# ngh-power.net
KiCad netlist of a schematic drawn in Altium Designer
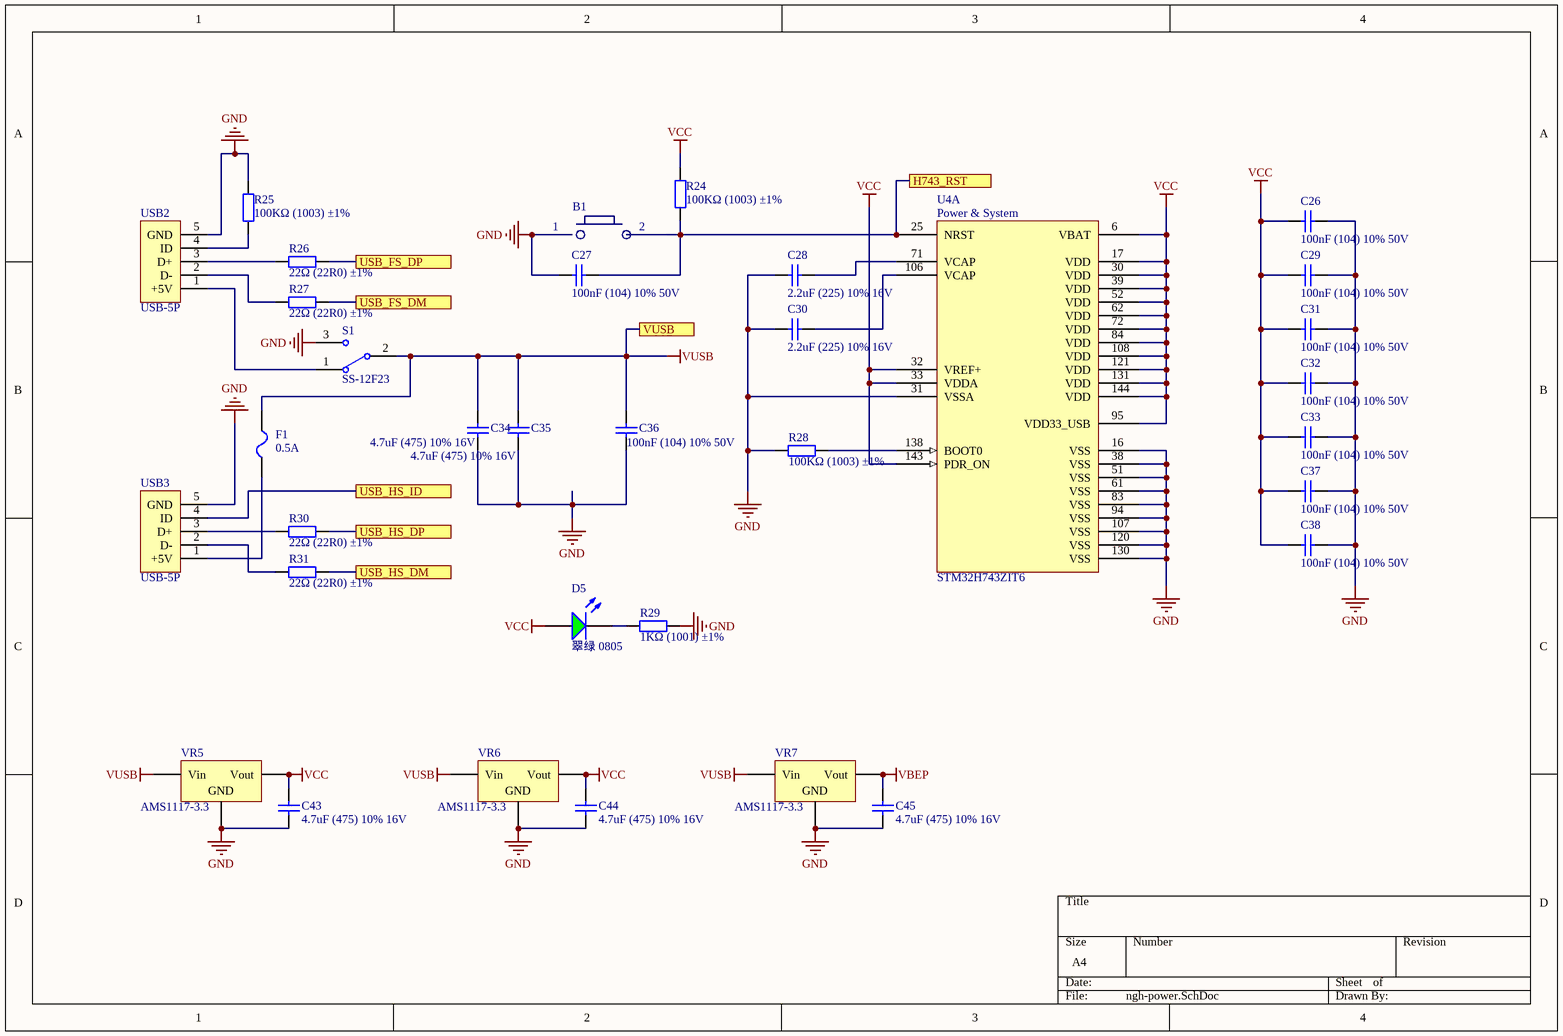
[diagram p0: ngh-power.SchDoc]

(export (version "E")
  (design (tool "Eeschema 10.0.6"))
  (components
    (comp (ref "B1")
      (value "B1")
      (footprint "MetalButton")
      (libsource (lib "MetalButton") (part "MetalButton"))
    )
    (comp (ref "C26")
      (value "100nF (104) 10% 50V")
      (footprint "0603_C")
      (description "贴片电容")
      (libsource (lib "Miscellaneous Devices LC") (part "0603 100nF (104) 10% 50V"))
    )
    (comp (ref "C27")
      (value "100nF (104) 10% 50V")
      (footprint "0603_C")
      (description "贴片电容")
      (libsource (lib "Miscellaneous Devices LC") (part "0603 100nF (104) 10% 50V"))
    )
    (comp (ref "C28")
      (value "2.2uF (225) 10% 16V")
      (footprint "0603_C")
      (description "贴片电容")
      (libsource (lib "Miscellaneous Devices LC") (part "0603 2.2uF (225) 10% 16V"))
    )
    (comp (ref "C29")
      (value "100nF (104) 10% 50V")
      (footprint "0603_C")
      (description "贴片电容")
      (libsource (lib "Miscellaneous Devices LC") (part "0603 100nF (104) 10% 50V"))
    )
    (comp (ref "C30")
      (value "2.2uF (225) 10% 16V")
      (footprint "0603_C")
      (description "贴片电容")
      (libsource (lib "Miscellaneous Devices LC") (part "0603 2.2uF (225) 10% 16V"))
    )
    (comp (ref "C31")
      (value "100nF (104) 10% 50V")
      (footprint "0603_C")
      (description "贴片电容")
      (libsource (lib "Miscellaneous Devices LC") (part "0603 100nF (104) 10% 50V"))
    )
    (comp (ref "C32")
      (value "100nF (104) 10% 50V")
      (footprint "0603_C")
      (description "贴片电容")
      (libsource (lib "Miscellaneous Devices LC") (part "0603 100nF (104) 10% 50V"))
    )
    (comp (ref "C33")
      (value "100nF (104) 10% 50V")
      (footprint "0603_C")
      (description "贴片电容")
      (libsource (lib "Miscellaneous Devices LC") (part "0603 100nF (104) 10% 50V"))
    )
    (comp (ref "C34")
      (value "4.7uF (475) 10% 16V")
      (footprint "0603_C")
      (description "贴片电容")
      (libsource (lib "Miscellaneous Devices LC") (part "0603 4.7uF (475) 10% 16V"))
    )
    (comp (ref "C35")
      (value "4.7uF (475) 10% 16V")
      (footprint "0603_C")
      (description "贴片电容")
      (libsource (lib "Miscellaneous Devices LC") (part "0603 4.7uF (475) 10% 16V"))
    )
    (comp (ref "C36")
      (value "100nF (104) 10% 50V")
      (footprint "0603_C")
      (description "贴片电容")
      (libsource (lib "Miscellaneous Devices LC") (part "0603 100nF (104) 10% 50V"))
    )
    (comp (ref "C37")
      (value "100nF (104) 10% 50V")
      (footprint "0603_C")
      (description "贴片电容")
      (libsource (lib "Miscellaneous Devices LC") (part "0603 100nF (104) 10% 50V"))
    )
    (comp (ref "C38")
      (value "100nF (104) 10% 50V")
      (footprint "0603_C")
      (description "贴片电容")
      (libsource (lib "Miscellaneous Devices LC") (part "0603 100nF (104) 10% 50V"))
    )
    (comp (ref "C43")
      (value "4.7uF (475) 10% 16V")
      (footprint "0603_C")
      (description "贴片电容")
      (libsource (lib "Miscellaneous Devices LC") (part "0603 4.7uF (475) 10% 16V"))
    )
    (comp (ref "C44")
      (value "4.7uF (475) 10% 16V")
      (footprint "0603_C")
      (description "贴片电容")
      (libsource (lib "Miscellaneous Devices LC") (part "0603 4.7uF (475) 10% 16V"))
    )
    (comp (ref "C45")
      (value "4.7uF (475) 10% 16V")
      (footprint "0603_C")
      (description "贴片电容")
      (libsource (lib "Miscellaneous Devices LC") (part "0603 4.7uF (475) 10% 16V"))
    )
    (comp (ref "D5")
      (value "翠绿 0805")
      (footprint "0805_LED_S1")
      (description "发光二极管")
      (libsource (lib "Miscellaneous Devices LC") (part "0805 翠绿"))
    )
    (comp (ref "F1")
      (value "0.5A")
      (footprint "FU 0603")
      (description "贴片保险丝")
      (fields (field (name "版权归属") "源创客"))
      (libsource (lib "10.1 - 保险丝-晶振") (part "FU"))
    )
    (comp (ref "R24")
      (value "100KΩ (1003) ±1%")
      (footprint "0603_R")
      (description "贴片电阻")
      (libsource (lib "Miscellaneous Devices LC") (part "0603 100KΩ (1003) 1%"))
    )
    (comp (ref "R25")
      (value "100KΩ (1003) ±1%")
      (footprint "0603_R")
      (description "贴片电阻")
      (libsource (lib "Miscellaneous Devices LC") (part "0603 100KΩ (1003) 1%"))
    )
    (comp (ref "R26")
      (value "22Ω (22R0) ±1%")
      (footprint "0603_R")
      (description "贴片电阻")
      (libsource (lib "Miscellaneous Devices LC") (part "0603 22Ω (22R0) 1%"))
    )
    (comp (ref "R27")
      (value "22Ω (22R0) ±1%")
      (footprint "0603_R")
      (description "贴片电阻")
      (libsource (lib "Miscellaneous Devices LC") (part "0603 22Ω (22R0) 1%"))
    )
    (comp (ref "R28")
      (value "100KΩ (1003) ±1%")
      (footprint "0603_R")
      (description "贴片电阻")
      (libsource (lib "") (part "0603 100KΩ (1003) 1%_1"))
    )
    (comp (ref "R29")
      (value "1KΩ (1001) ±1%")
      (footprint "0603_R")
      (description "贴片电阻")
      (libsource (lib "Miscellaneous Devices LC") (part "0603 1KΩ (1001) 1%"))
    )
    (comp (ref "R30")
      (value "22Ω (22R0) ±1%")
      (footprint "0603_R")
      (description "贴片电阻")
      (libsource (lib "Miscellaneous Devices LC") (part "0603 22Ω (22R0) 1%"))
    )
    (comp (ref "R31")
      (value "22Ω (22R0) ±1%")
      (footprint "0603_R")
      (description "贴片电阻")
      (libsource (lib "Miscellaneous Devices LC") (part "0603 22Ω (22R0) 1%"))
    )
    (comp (ref "S1")
      (value "SS-12F23")
      (footprint "SS-12F23")
      (description "1路波动开关")
      (fields (field (name "版权归属") "源创客"))
      (libsource (lib "5.1   - 按键-开关") (part "SSW-1P"))
    )
    (comp (ref "U4")
      (value "STM32H743ZIT6")
      (footprint "LQFP-144_20x20")
      (libsource (lib "STM32H743ZI") (part "STM32H743ZIT6"))
    )
    (comp (ref "USB2")
      (value "USB-5P")
      (footprint "USB-MICRO_D")
      (description "微型USB母座")
      (fields (field (name "版权归属") "源创客"))
      (libsource (lib "4.1   - 接口类") (part "USB-5P"))
    )
    (comp (ref "USB3")
      (value "USB-5P")
      (footprint "USB-MICRO_D")
      (description "微型USB母座")
      (fields (field (name "版权归属") "源创客"))
      (libsource (lib "4.1   - 接口类") (part "USB-5P"))
    )
    (comp (ref "VR5")
      (value "AMS1117-3.3")
      (footprint "SOT-223")
      (description "低压差线性稳压(LDO)")
      (libsource (lib "Miscellaneous Devices LC") (part "SOT-223 AMS1117-3.3"))
    )
    (comp (ref "VR6")
      (value "AMS1117-3.3")
      (footprint "SOT-223")
      (description "低压差线性稳压(LDO)")
      (libsource (lib "Miscellaneous Devices LC") (part "SOT-223 AMS1117-3.3"))
    )
    (comp (ref "VR7")
      (value "AMS1117-3.3")
      (footprint "SOT-223")
      (description "低压差线性稳压(LDO)")
      (libsource (lib "Miscellaneous Devices LC") (part "SOT-223 AMS1117-3.3"))
    )
  )
  (nets
    (net (code "1") (name "/H743_RST") (class "Default")
      (node (ref "B1") (pin "2") (pinfunction "2_2") (pintype "passive"))
      (node (ref "C27") (pin "2") (pinfunction "2_2") (pintype "passive"))
      (node (ref "R24") (pin "1") (pinfunction "1_1") (pintype "passive"))
      (node (ref "U4") (pin "25") (pinfunction "NRST_25") (pintype "power_in"))
    )
    (net (code "2") (name "/USB_FS_DM") (class "Default")
      (node (ref "R27") (pin "2") (pinfunction "2_2") (pintype "passive"))
    )
    (net (code "3") (name "/USB_FS_DP") (class "Default")
      (node (ref "R26") (pin "2") (pinfunction "2_2") (pintype "passive"))
    )
    (net (code "4") (name "/USB_HS_DM") (class "Default")
      (node (ref "R31") (pin "2") (pinfunction "2_2") (pintype "passive"))
    )
    (net (code "5") (name "/USB_HS_DP") (class "Default")
      (node (ref "R30") (pin "2") (pinfunction "2_2") (pintype "passive"))
    )
    (net (code "6") (name "/USB_HS_ID") (class "Default")
      (node (ref "USB3") (pin "4") (pinfunction "ID_4") (pintype "passive"))
    )
    (net (code "7") (name "GND") (class "Default")
      (node (ref "B1") (pin "1") (pinfunction "1_1") (pintype "passive"))
      (node (ref "C26") (pin "1") (pinfunction "1_1") (pintype "passive"))
      (node (ref "C27") (pin "1") (pinfunction "1_1") (pintype "passive"))
      (node (ref "C28") (pin "1") (pinfunction "1_1") (pintype "passive"))
      (node (ref "C29") (pin "1") (pinfunction "1_1") (pintype "passive"))
      (node (ref "C30") (pin "1") (pinfunction "1_1") (pintype "passive"))
      (node (ref "C31") (pin "1") (pinfunction "1_1") (pintype "passive"))
      (node (ref "C32") (pin "1") (pinfunction "1_1") (pintype "passive"))
      (node (ref "C33") (pin "1") (pinfunction "1_1") (pintype "passive"))
      (node (ref "C34") (pin "1") (pinfunction "1_1") (pintype "passive"))
      (node (ref "C35") (pin "1") (pinfunction "1_1") (pintype "passive"))
      (node (ref "C36") (pin "1") (pinfunction "1_1") (pintype "passive"))
      (node (ref "C37") (pin "1") (pinfunction "1_1") (pintype "passive"))
      (node (ref "C38") (pin "1") (pinfunction "1_1") (pintype "passive"))
      (node (ref "C43") (pin "1") (pinfunction "1_1") (pintype "passive"))
      (node (ref "C44") (pin "1") (pinfunction "1_1") (pintype "passive"))
      (node (ref "C45") (pin "1") (pinfunction "1_1") (pintype "passive"))
      (node (ref "R25") (pin "2") (pinfunction "2_2") (pintype "passive"))
      (node (ref "R28") (pin "2") (pinfunction "2_2") (pintype "passive"))
      (node (ref "R29") (pin "1") (pinfunction "1_1") (pintype "passive"))
      (node (ref "S1") (pin "3") (pinfunction "3_3") (pintype "passive"))
      (node (ref "U4") (pin "107") (pinfunction "VSS_107") (pintype "power_in"))
      (node (ref "U4") (pin "120") (pinfunction "VSS_120") (pintype "power_in"))
      (node (ref "U4") (pin "130") (pinfunction "VSS_130") (pintype "power_in"))
      (node (ref "U4") (pin "16") (pinfunction "VSS_16") (pintype "power_in"))
      (node (ref "U4") (pin "31") (pinfunction "VSSA_31") (pintype "power_in"))
      (node (ref "U4") (pin "38") (pinfunction "VSS_38") (pintype "power_in"))
      (node (ref "U4") (pin "51") (pinfunction "VSS_51") (pintype "power_in"))
      (node (ref "U4") (pin "61") (pinfunction "VSS_61") (pintype "power_in"))
      (node (ref "U4") (pin "83") (pinfunction "VSS_83") (pintype "power_in"))
      (node (ref "U4") (pin "94") (pinfunction "VSS_94") (pintype "power_in"))
      (node (ref "USB2") (pin "5") (pinfunction "GND_5") (pintype "passive"))
      (node (ref "USB3") (pin "5") (pinfunction "GND_5") (pintype "passive"))
      (node (ref "VR5") (pin "1") (pinfunction "GND_1") (pintype "passive"))
      (node (ref "VR6") (pin "1") (pinfunction "GND_1") (pintype "passive"))
      (node (ref "VR7") (pin "1") (pinfunction "GND_1") (pintype "passive"))
    )
    (net (code "8") (name "Net-(C28-Pad2)") (class "Default")
      (node (ref "C28") (pin "2") (pinfunction "2_2") (pintype "passive"))
      (node (ref "U4") (pin "71") (pinfunction "VCAP_71") (pintype "power_in"))
    )
    (net (code "9") (name "Net-(C30-Pad2)") (class "Default")
      (node (ref "C30") (pin "2") (pinfunction "2_2") (pintype "passive"))
      (node (ref "U4") (pin "106") (pinfunction "VCAP_106") (pintype "power_in"))
    )
    (net (code "10") (name "Net-(D5-PadK)") (class "Default")
      (node (ref "D5") (pin "K") (pinfunction "K_K") (pintype "passive"))
      (node (ref "R29") (pin "2") (pinfunction "2_2") (pintype "passive"))
    )
    (net (code "11") (name "Net-(U4A-BOOT0)") (class "Default")
      (node (ref "R28") (pin "1") (pinfunction "1_1") (pintype "passive"))
      (node (ref "U4") (pin "138") (pinfunction "BOOT0_138") (pintype "input"))
    )
    (net (code "12") (name "Net-(USB2-+5V)") (class "Default")
      (node (ref "S1") (pin "1") (pinfunction "1_1") (pintype "passive"))
      (node (ref "USB2") (pin "1") (pinfunction "+5V_1") (pintype "passive"))
    )
    (net (code "13") (name "Net-(USB2-D+)") (class "Default")
      (node (ref "R26") (pin "1") (pinfunction "1_1") (pintype "passive"))
      (node (ref "USB2") (pin "3") (pinfunction "D+_3") (pintype "passive"))
    )
    (net (code "14") (name "Net-(USB2-D-)") (class "Default")
      (node (ref "R27") (pin "1") (pinfunction "1_1") (pintype "passive"))
      (node (ref "USB2") (pin "2") (pinfunction "D-_2") (pintype "passive"))
    )
    (net (code "15") (name "Net-(USB2-ID)") (class "Default")
      (node (ref "R25") (pin "1") (pinfunction "1_1") (pintype "passive"))
      (node (ref "USB2") (pin "4") (pinfunction "ID_4") (pintype "passive"))
    )
    (net (code "16") (name "Net-(USB3-+5V)") (class "Default")
      (node (ref "F1") (pin "1") (pinfunction "1_1") (pintype "passive"))
      (node (ref "USB3") (pin "1") (pinfunction "+5V_1") (pintype "passive"))
    )
    (net (code "17") (name "Net-(USB3-D+)") (class "Default")
      (node (ref "R30") (pin "1") (pinfunction "1_1") (pintype "passive"))
      (node (ref "USB3") (pin "3") (pinfunction "D+_3") (pintype "passive"))
    )
    (net (code "18") (name "Net-(USB3-D-)") (class "Default")
      (node (ref "R31") (pin "1") (pinfunction "1_1") (pintype "passive"))
      (node (ref "USB3") (pin "2") (pinfunction "D-_2") (pintype "passive"))
    )
    (net (code "19") (name "VBEP") (class "Default")
      (node (ref "C45") (pin "2") (pinfunction "2_2") (pintype "passive"))
      (node (ref "VR7") (pin "2") (pinfunction "Vout_2") (pintype "passive"))
    )
    (net (code "20") (name "VCC") (class "Default")
      (node (ref "C26") (pin "2") (pinfunction "2_2") (pintype "passive"))
      (node (ref "C29") (pin "2") (pinfunction "2_2") (pintype "passive"))
      (node (ref "C31") (pin "2") (pinfunction "2_2") (pintype "passive"))
      (node (ref "C32") (pin "2") (pinfunction "2_2") (pintype "passive"))
      (node (ref "C33") (pin "2") (pinfunction "2_2") (pintype "passive"))
      (node (ref "C37") (pin "2") (pinfunction "2_2") (pintype "passive"))
      (node (ref "C38") (pin "2") (pinfunction "2_2") (pintype "passive"))
      (node (ref "C43") (pin "2") (pinfunction "2_2") (pintype "passive"))
      (node (ref "C44") (pin "2") (pinfunction "2_2") (pintype "passive"))
      (node (ref "D5") (pin "A") (pinfunction "A_A") (pintype "passive"))
      (node (ref "R24") (pin "2") (pinfunction "2_2") (pintype "passive"))
      (node (ref "U4") (pin "108") (pinfunction "VDD_108") (pintype "power_in"))
      (node (ref "U4") (pin "121") (pinfunction "VDD_121") (pintype "power_in"))
      (node (ref "U4") (pin "131") (pinfunction "VDD_131") (pintype "power_in"))
      (node (ref "U4") (pin "143") (pinfunction "PDR_ON_143") (pintype "input"))
      (node (ref "U4") (pin "144") (pinfunction "VDD_144") (pintype "power_in"))
      (node (ref "U4") (pin "17") (pinfunction "VDD_17") (pintype "power_in"))
      (node (ref "U4") (pin "30") (pinfunction "VDD_30") (pintype "power_in"))
      (node (ref "U4") (pin "32") (pinfunction "VREF+_32") (pintype "power_in"))
      (node (ref "U4") (pin "33") (pinfunction "VDDA_33") (pintype "power_in"))
      (node (ref "U4") (pin "39") (pinfunction "VDD_39") (pintype "power_in"))
      (node (ref "U4") (pin "52") (pinfunction "VDD_52") (pintype "power_in"))
      (node (ref "U4") (pin "6") (pinfunction "VBAT_6") (pintype "power_in"))
      (node (ref "U4") (pin "62") (pinfunction "VDD_62") (pintype "power_in"))
      (node (ref "U4") (pin "72") (pinfunction "VDD_72") (pintype "power_in"))
      (node (ref "U4") (pin "84") (pinfunction "VDD_84") (pintype "power_in"))
      (node (ref "U4") (pin "95") (pinfunction "VDD33_USB_95") (pintype "power_in"))
      (node (ref "VR5") (pin "2") (pinfunction "Vout_2") (pintype "passive"))
      (node (ref "VR6") (pin "2") (pinfunction "Vout_2") (pintype "passive"))
    )
    (net (code "21") (name "VUSB") (class "Default")
      (node (ref "C34") (pin "2") (pinfunction "2_2") (pintype "passive"))
      (node (ref "C35") (pin "2") (pinfunction "2_2") (pintype "passive"))
      (node (ref "C36") (pin "2") (pinfunction "2_2") (pintype "passive"))
      (node (ref "F1") (pin "2") (pinfunction "2_2") (pintype "passive"))
      (node (ref "S1") (pin "2") (pinfunction "2_2") (pintype "passive"))
      (node (ref "VR5") (pin "3") (pinfunction "Vin_3") (pintype "passive"))
      (node (ref "VR6") (pin "3") (pinfunction "Vin_3") (pintype "passive"))
      (node (ref "VR7") (pin "3") (pinfunction "Vin_3") (pintype "passive"))
    )
  )
)
